# Spar7_rebuild.net
KiCad netlist of a schematic drawn in EAGLE
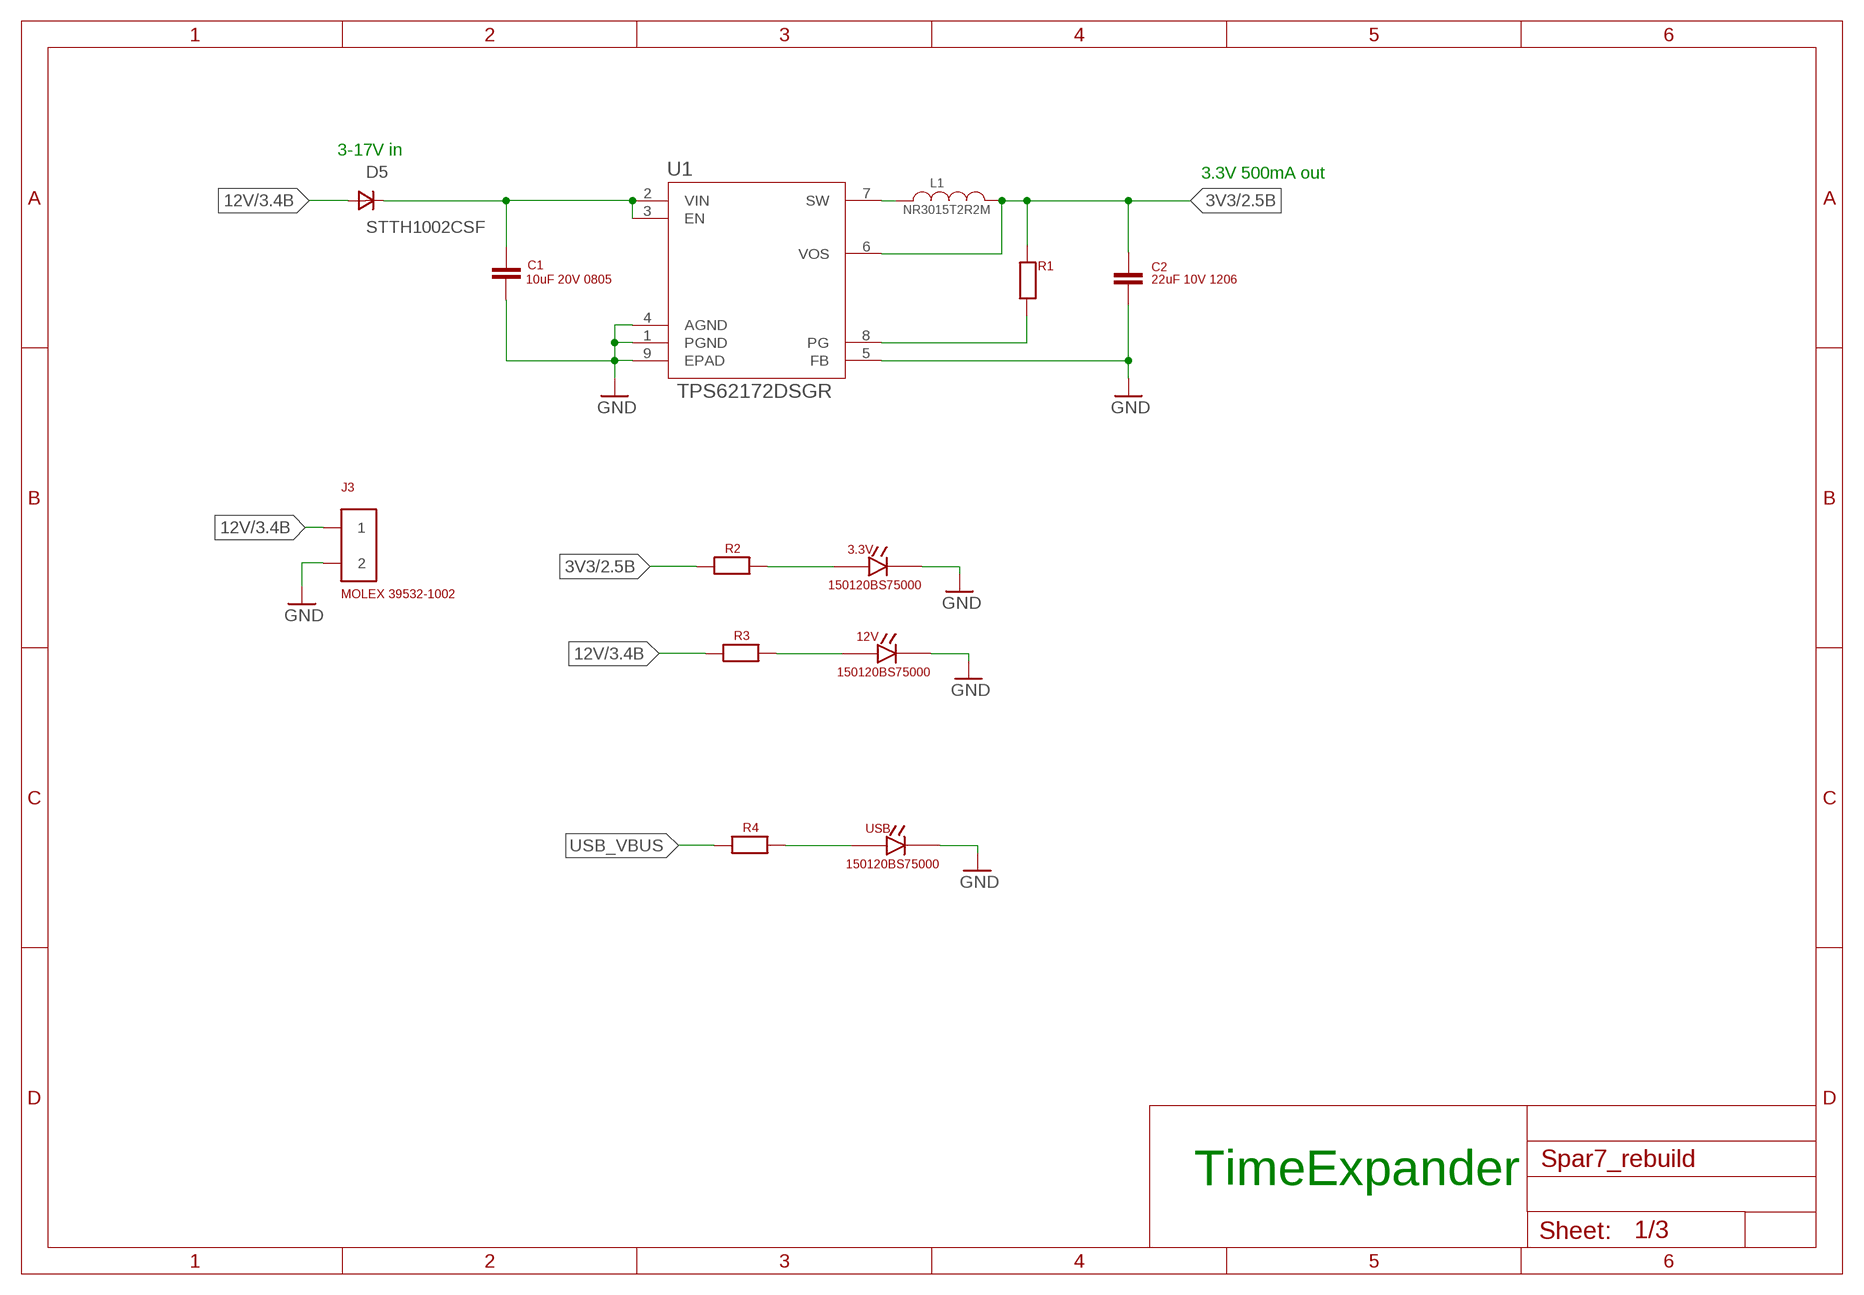
[diagram p0: schematic, sheet 1]
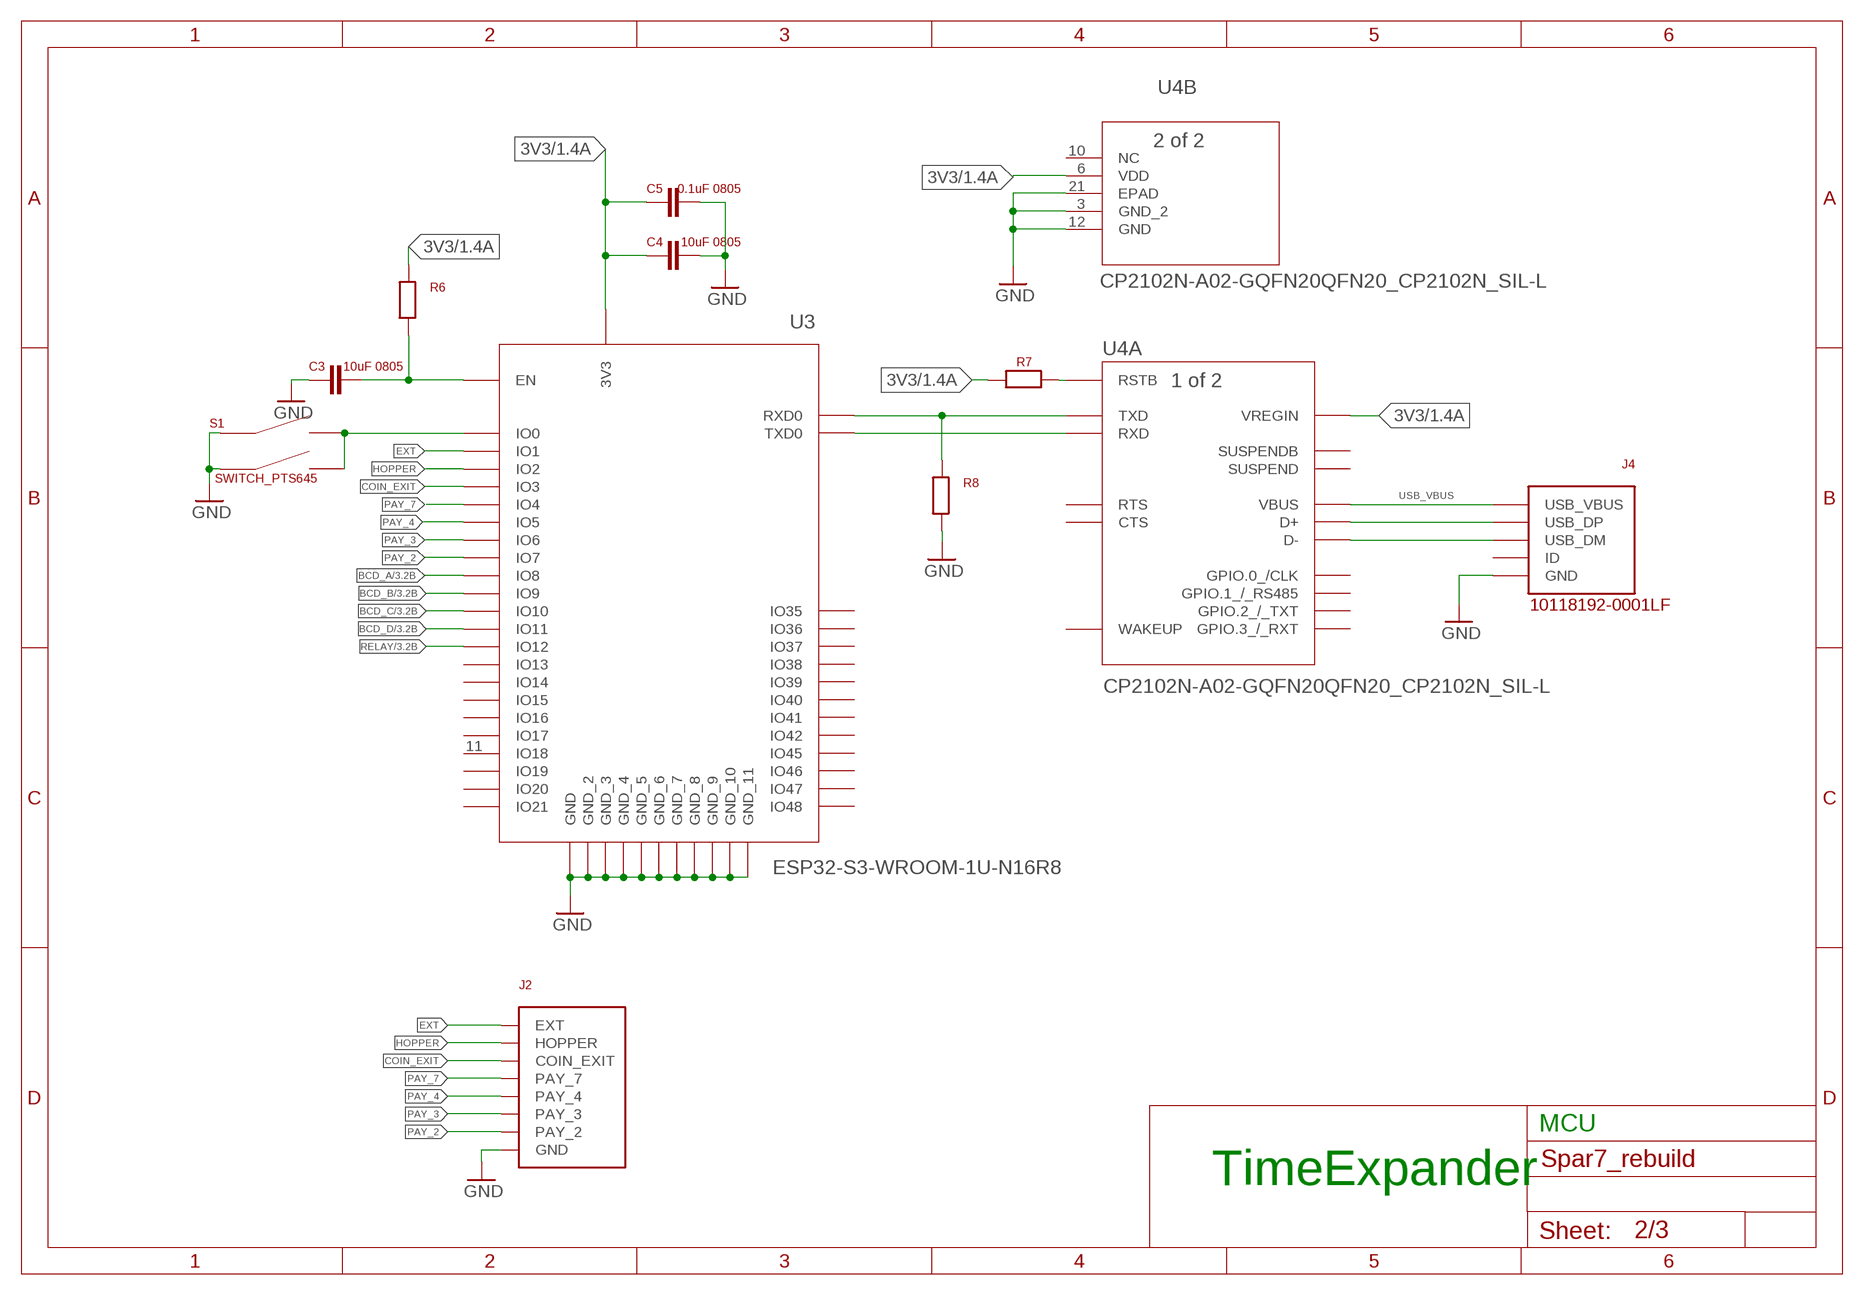
[diagram p1: schematic, sheet 2]
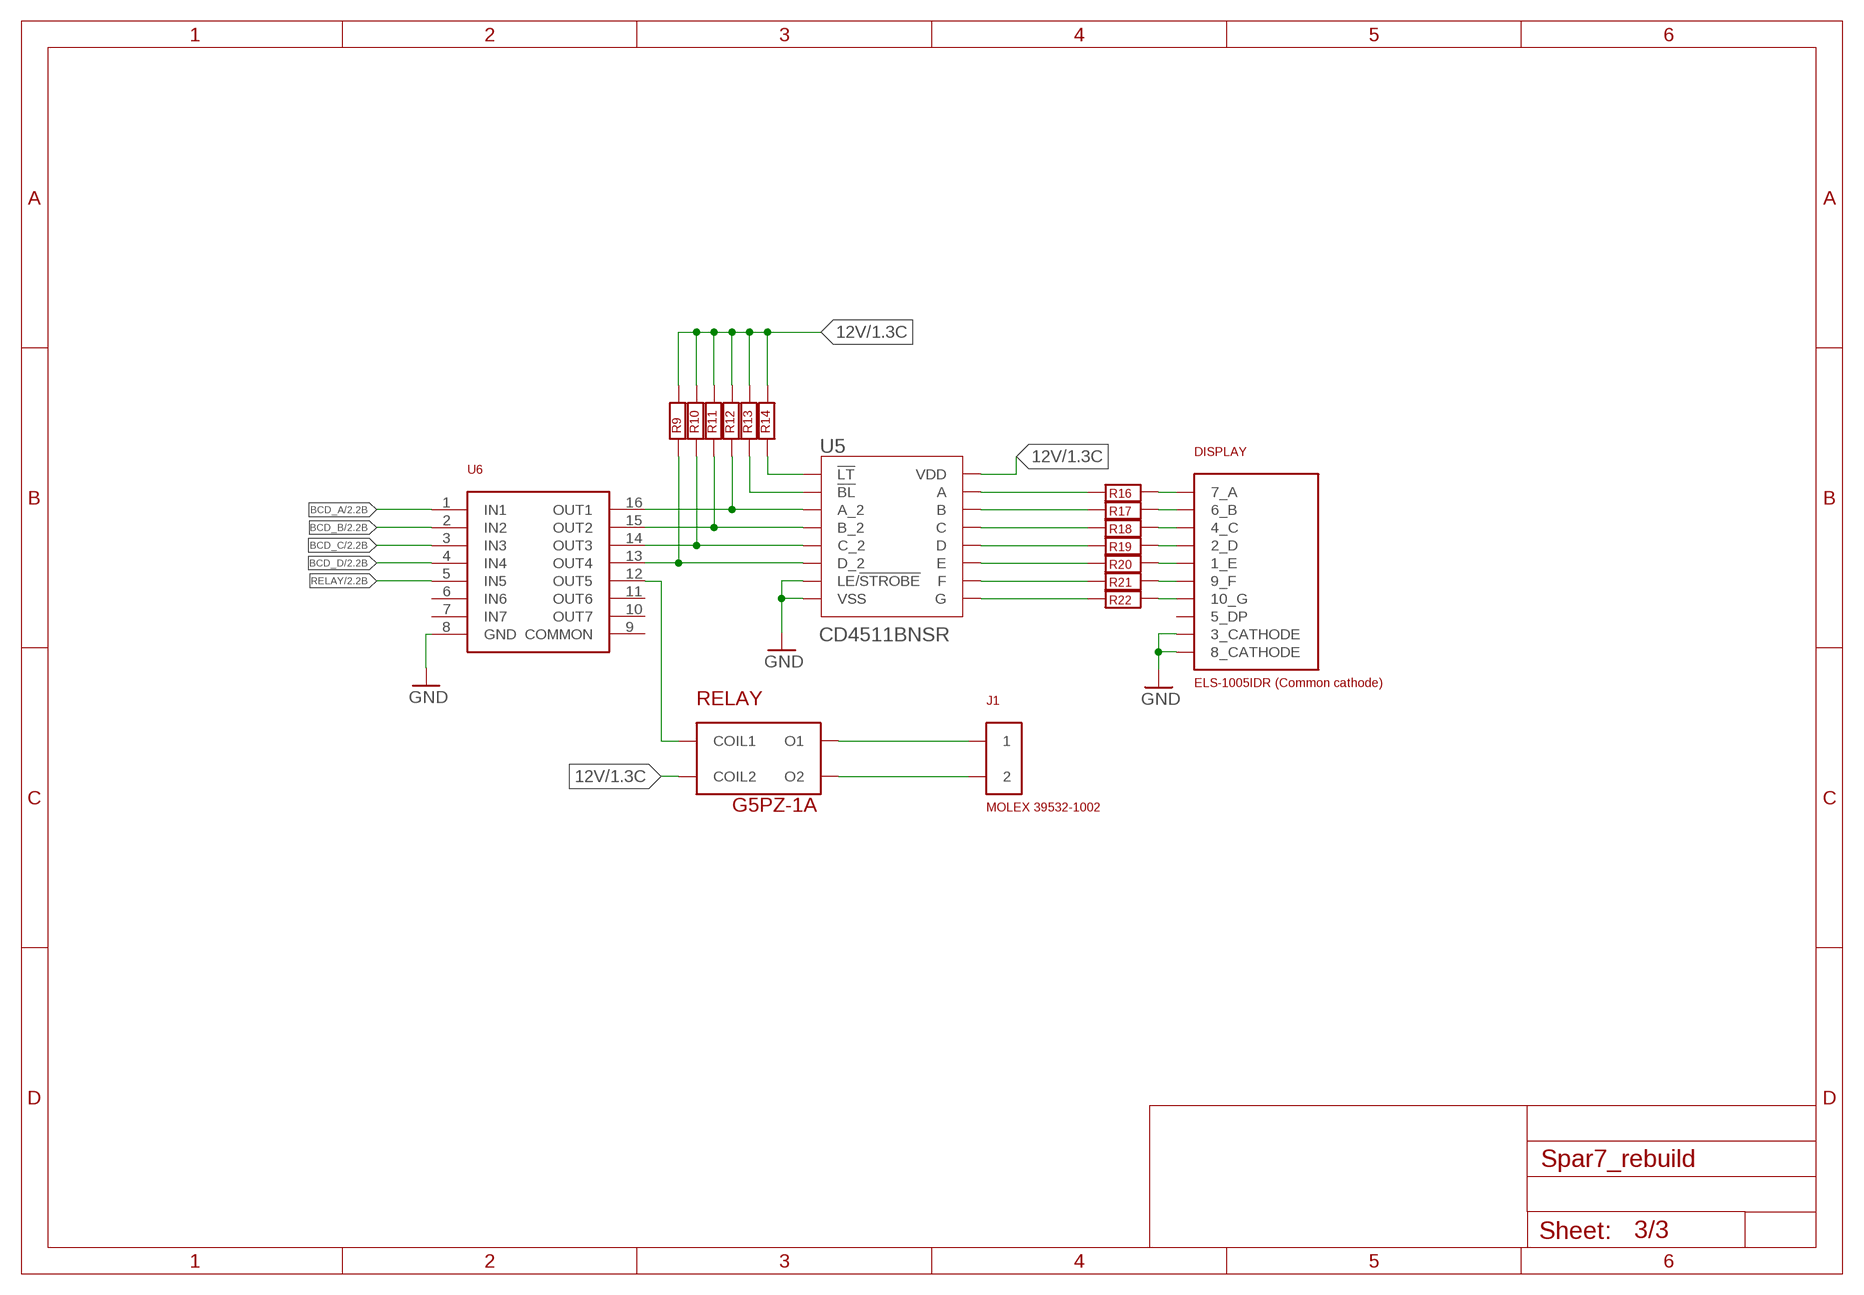
[diagram p2: schematic, sheet 3]

(export (version "E")
  (design (tool "Eeschema 10.0.6"))
  (components
    (comp (ref "C3")
      (value "10uF 0805")
      (footprint "eagle-import:CAP_0805")
      (libsource (lib "eagle-import") (part "CAPACITOR0805"))
    )
    (comp (ref "C4")
      (value "10uF 0805")
      (footprint "eagle-import:CAP_0805")
      (libsource (lib "eagle-import") (part "CAPACITOR0805"))
    )
    (comp (ref "C5")
      (value "0.1uF 0805")
      (footprint "eagle-import:CAP_0805")
      (libsource (lib "eagle-import") (part "CAPACITOR0805"))
    )
    (comp (ref "J2")
      (value "SPAR7_REWIRED_TERM_BLOCK")
      (footprint "eagle-import:SPAR7_REWIRED_TERM_BLOCK")
      (libsource (lib "eagle-import") (part "SPAR7_REWIRED_TERM_BLOCK"))
    )
    (comp (ref "J4")
      (value "10118192-0001LF")
      (footprint "eagle-import:USB_RCPT_10118192-0001LF")
      (libsource (lib "eagle-import") (part "USB_RCPT_10118192-0001LF"))
    )
    (comp (ref "R6")
      (value "RESISTOR0402")
      (footprint "eagle-import:RES_0402")
      (libsource (lib "eagle-import") (part "RESISTOR0402"))
    )
    (comp (ref "R7")
      (value "RESISTOR0402")
      (footprint "eagle-import:RES_0402")
      (libsource (lib "eagle-import") (part "RESISTOR0402"))
    )
    (comp (ref "R8")
      (value "RESISTOR0402")
      (footprint "eagle-import:RES_0402")
      (libsource (lib "eagle-import") (part "RESISTOR0402"))
    )
    (comp (ref "S1")
      (value "SWITCH_PTS645")
      (footprint "eagle-import:SWITCH_PTS645_EE_NBIOT_01")
      (libsource (lib "eagle-import") (part "SWITCH_PTS645"))
    )
    (comp (ref "U3")
      (value "ESP32-S3-WROOM-1U-N16R8")
      (footprint "eagle-import:ESP32­S3­WROOM­1U_EXP")
      (fields (field (name "COPYRIGHT") "Copyright (C) 2023 Ultra Librarian. All rights reserved."))
      (libsource (lib "eagle-import") (part "ESP32-S3-WROOM-1U-N16R8"))
    )
    (comp (ref "U4")
      (value "CP2102N-A02-GQFN20QFN20_CP2102N_SIL-L")
      (footprint "eagle-import:QFN20_CP2102N_SIL-L")
      (fields
        (field (name "MANUFACTURER_PART_NUMBER") "CP2102N-A02-GQFN20")
        (field (name "COPYRIGHT") "Copyright (C) 2023 Ultra Librarian. All rights reserved.")
      )
      (libsource (lib "eagle-import") (part "CP2102N-A02-GQFN20QFN20_CP2102N_SIL-L"))
    )
    (comp (ref "3.3V")
      (value "150120BS75000")
      (footprint "eagle-import:150120BS75000")
      (libsource (lib "eagle-import") (part "LED150120BS75000"))
    )
    (comp (ref "12V")
      (value "150120BS75000")
      (footprint "eagle-import:150120BS75000")
      (libsource (lib "eagle-import") (part "LED150120BS75000"))
    )
    (comp (ref "C1")
      (value "10uF 20V 0805")
      (footprint "eagle-import:CAP_0805")
      (libsource (lib "eagle-import") (part "CAPACITOR0805"))
    )
    (comp (ref "C2")
      (value "22uF 10V 1206")
      (footprint "eagle-import:CAP_1206")
      (libsource (lib "eagle-import") (part "CAPACITOR1206"))
    )
    (comp (ref "D5")
      (value "STTH1002CSF")
      (footprint "eagle-import:DIODE_STTH1002CSF")
      (libsource (lib "eagle-import") (part "DIODESTTH1002CSF"))
    )
    (comp (ref "J3")
      (value "MOLEX-39532-1002")
      (footprint "eagle-import:MOLEX-39532-1002")
      (libsource (lib "eagle-import") (part "MOLEX-39532-1002"))
    )
    (comp (ref "L1")
      (value "NR3015T2R2M")
      (footprint "eagle-import:IND_TAIYO_NR3015_TAY")
      (libsource (lib "eagle-import") (part "NR3015T2R2M"))
    )
    (comp (ref "R1")
      (value "RESISTOR0402")
      (footprint "eagle-import:RES_0402")
      (libsource (lib "eagle-import") (part "RESISTOR0402"))
    )
    (comp (ref "R2")
      (value "RESISTOR0402")
      (footprint "eagle-import:RES_0402")
      (libsource (lib "eagle-import") (part "RESISTOR0402"))
    )
    (comp (ref "R3")
      (value "RESISTOR0402")
      (footprint "eagle-import:RES_0402")
      (libsource (lib "eagle-import") (part "RESISTOR0402"))
    )
    (comp (ref "R4")
      (value "RESISTOR0402")
      (footprint "eagle-import:RES_0402")
      (libsource (lib "eagle-import") (part "RESISTOR0402"))
    )
    (comp (ref "U1")
      (value "TPS62172DSGR")
      (footprint "eagle-import:DSG8_1P6X0P9")
      (fields
        (field (name "GENERIC_PART_NUMBER") "TPS62173")
        (field (name "MANUFACTURER") "Texas Instruments")
        (field (name "MANUFACTURER_PART_NUMBER") "TPS62173DSGR")
      )
      (libsource (lib "eagle-import") (part "TPS62173DSGR"))
    )
    (comp (ref "USB")
      (value "150120BS75000")
      (footprint "eagle-import:150120BS75000")
      (libsource (lib "eagle-import") (part "LED150120BS75000"))
    )
    (comp (ref "DISPLAY")
      (value "ELS-1005IDR-SA10-21EWA")
      (footprint "eagle-import:ELS-1005IDR-SA10-21EWA")
      (libsource (lib "eagle-import") (part "ELS-1005IDR-SA10-21EWA"))
    )
    (comp (ref "J1")
      (value "MOLEX-39532-1002")
      (footprint "eagle-import:MOLEX-39532-1002")
      (libsource (lib "eagle-import") (part "MOLEX-39532-1002"))
    )
    (comp (ref "R9")
      (value "RESISTOR0402")
      (footprint "eagle-import:RES_0402")
      (libsource (lib "eagle-import") (part "RESISTOR0402"))
    )
    (comp (ref "R10")
      (value "RESISTOR0402")
      (footprint "eagle-import:RES_0402")
      (libsource (lib "eagle-import") (part "RESISTOR0402"))
    )
    (comp (ref "R11")
      (value "RESISTOR0402")
      (footprint "eagle-import:RES_0402")
      (libsource (lib "eagle-import") (part "RESISTOR0402"))
    )
    (comp (ref "R12")
      (value "RESISTOR0402")
      (footprint "eagle-import:RES_0402")
      (libsource (lib "eagle-import") (part "RESISTOR0402"))
    )
    (comp (ref "R13")
      (value "RESISTOR0402")
      (footprint "eagle-import:RES_0402")
      (libsource (lib "eagle-import") (part "RESISTOR0402"))
    )
    (comp (ref "R14")
      (value "RESISTOR0402")
      (footprint "eagle-import:RES_0402")
      (libsource (lib "eagle-import") (part "RESISTOR0402"))
    )
    (comp (ref "R16")
      (value "RESISTOR0402")
      (footprint "eagle-import:RES_0402")
      (libsource (lib "eagle-import") (part "RESISTOR0402"))
    )
    (comp (ref "R17")
      (value "RESISTOR0402")
      (footprint "eagle-import:RES_0402")
      (libsource (lib "eagle-import") (part "RESISTOR0402"))
    )
    (comp (ref "R18")
      (value "RESISTOR0402")
      (footprint "eagle-import:RES_0402")
      (libsource (lib "eagle-import") (part "RESISTOR0402"))
    )
    (comp (ref "R19")
      (value "RESISTOR0402")
      (footprint "eagle-import:RES_0402")
      (libsource (lib "eagle-import") (part "RESISTOR0402"))
    )
    (comp (ref "R20")
      (value "RESISTOR0402")
      (footprint "eagle-import:RES_0402")
      (libsource (lib "eagle-import") (part "RESISTOR0402"))
    )
    (comp (ref "R21")
      (value "RESISTOR0402")
      (footprint "eagle-import:RES_0402")
      (libsource (lib "eagle-import") (part "RESISTOR0402"))
    )
    (comp (ref "R22")
      (value "RESISTOR0402")
      (footprint "eagle-import:RES_0402")
      (libsource (lib "eagle-import") (part "RESISTOR0402"))
    )
    (comp (ref "RELAY")
      (value "G5PZ-1A_RELAY")
      (footprint "eagle-import:G5PZ-1A_RELAY")
      (libsource (lib "eagle-import") (part "G5PZ-1A_RELAY"))
    )
    (comp (ref "U5")
      (value "CD4511BNSR")
      (footprint "eagle-import:NS16")
      (fields (field (name "COPYRIGHT") "Copyright (C) 2023 Ultra Librarian. All rights reserved."))
      (libsource (lib "eagle-import") (part "CD4511BNSR"))
    )
    (comp (ref "U6")
      (value "ULN2003D1013TR")
      (footprint "eagle-import:SO16-NARROW")
      (libsource (lib "eagle-import") (part "ULN2003D1013TR"))
    )
  )
  (nets
    (net (code "1") (name "3V3") (class "Default")
      (node (ref "C2") (pin "P$1") (pinfunction "1_P$1") (pintype "passive"))
      (node (ref "C4") (pin "P$1") (pinfunction "1_P$1") (pintype "passive"))
      (node (ref "C5") (pin "P$1") (pinfunction "1_P$1") (pintype "passive"))
      (node (ref "L1") (pin "1") (pinfunction "1_1") (pintype "passive"))
      (node (ref "R1") (pin "P$1") (pinfunction "P$1_P$1") (pintype "bidirectional"))
      (node (ref "R2") (pin "P$1") (pinfunction "P$1_P$1") (pintype "bidirectional"))
      (node (ref "R6") (pin "P$2") (pinfunction "P$2_P$2") (pintype "bidirectional"))
      (node (ref "R7") (pin "P$1") (pinfunction "P$1_P$1") (pintype "bidirectional"))
      (node (ref "U1") (pin "6") (pinfunction "VOS_6") (pintype "input"))
      (node (ref "U3") (pin "2") (pinfunction "3V3_2") (pintype "power_in"))
      (node (ref "U4") (pin "6") (pinfunction "VDD_6") (pintype "power_in"))
      (node (ref "U4") (pin "7") (pinfunction "VREGIN_7") (pintype "passive"))
    )
    (net (code "2") (name "12V") (class "Default")
      (node (ref "D5") (pin "A1") (pinfunction "A_A1") (pintype "passive"))
      (node (ref "D5") (pin "A2") (pinfunction "A_A2") (pintype "passive"))
      (node (ref "J3") (pin "1") (pinfunction "1_1") (pintype "power_in"))
      (node (ref "R10") (pin "P$2") (pinfunction "P$2_P$2") (pintype "bidirectional"))
      (node (ref "R11") (pin "P$2") (pinfunction "P$2_P$2") (pintype "bidirectional"))
      (node (ref "R12") (pin "P$2") (pinfunction "P$2_P$2") (pintype "bidirectional"))
      (node (ref "R13") (pin "P$2") (pinfunction "P$2_P$2") (pintype "bidirectional"))
      (node (ref "R14") (pin "P$2") (pinfunction "P$2_P$2") (pintype "bidirectional"))
      (node (ref "R3") (pin "P$1") (pinfunction "P$1_P$1") (pintype "bidirectional"))
      (node (ref "R9") (pin "P$2") (pinfunction "P$2_P$2") (pintype "bidirectional"))
      (node (ref "RELAY") (pin "COIL2") (pinfunction "COIL2_COIL2") (pintype "power_in"))
      (node (ref "U5") (pin "16") (pinfunction "VDD_16") (pintype "power_in"))
    )
    (net (code "3") (name "BCD_A") (class "Default")
      (node (ref "U3") (pin "12") (pinfunction "IO8_12") (pintype "bidirectional"))
      (node (ref "U6") (pin "1") (pinfunction "IN1_1") (pintype "bidirectional"))
    )
    (net (code "4") (name "BCD_B") (class "Default")
      (node (ref "U3") (pin "17") (pinfunction "IO9_17") (pintype "bidirectional"))
      (node (ref "U6") (pin "2") (pinfunction "IN2_2") (pintype "bidirectional"))
    )
    (net (code "5") (name "BCD_C") (class "Default")
      (node (ref "U3") (pin "18") (pinfunction "IO10_18") (pintype "bidirectional"))
      (node (ref "U6") (pin "3") (pinfunction "IN3_3") (pintype "bidirectional"))
    )
    (net (code "6") (name "BCD_D") (class "Default")
      (node (ref "U3") (pin "19") (pinfunction "IO11_19") (pintype "bidirectional"))
      (node (ref "U6") (pin "4") (pinfunction "IN4_4") (pintype "bidirectional"))
    )
    (net (code "7") (name "COIN_EXIT") (class "Default")
      (node (ref "J2") (pin "COIN_EXIT") (pinfunction "COIN_EXIT_COIN_EXIT") (pintype "power_in"))
      (node (ref "U3") (pin "15") (pinfunction "IO3_15") (pintype "bidirectional"))
    )
    (net (code "8") (name "EXT") (class "Default")
      (node (ref "J2") (pin "EXT") (pinfunction "EXT_EXT") (pintype "power_in"))
      (node (ref "U3") (pin "39") (pinfunction "IO1_39") (pintype "bidirectional"))
    )
    (net (code "9") (name "GND") (class "Default")
      (node (ref "12V") (pin "C") (pinfunction "C_C") (pintype "passive"))
      (node (ref "3.3V") (pin "C") (pinfunction "C_C") (pintype "passive"))
      (node (ref "C1") (pin "P$2") (pinfunction "2_P$2") (pintype "passive"))
      (node (ref "C2") (pin "P$2") (pinfunction "2_P$2") (pintype "passive"))
      (node (ref "C3") (pin "P$1") (pinfunction "1_P$1") (pintype "passive"))
      (node (ref "C4") (pin "P$2") (pinfunction "2_P$2") (pintype "passive"))
      (node (ref "C5") (pin "P$2") (pinfunction "2_P$2") (pintype "passive"))
      (node (ref "DISPLAY") (pin "3_CATHODE") (pinfunction "3_CATHODE_3_CATHODE") (pintype "bidirectional"))
      (node (ref "DISPLAY") (pin "8_CATHODE") (pinfunction "8_CATHODE_8_CATHODE") (pintype "bidirectional"))
      (node (ref "J2") (pin "GND") (pinfunction "GND_GND") (pintype "power_in"))
      (node (ref "J3") (pin "2") (pinfunction "2_2") (pintype "power_in"))
      (node (ref "J4") (pin "GND") (pinfunction "GND_GND") (pintype "passive"))
      (node (ref "R8") (pin "P$1") (pinfunction "P$1_P$1") (pintype "bidirectional"))
      (node (ref "S1") (pin "A1") (pinfunction "A1_A1") (pintype "bidirectional"))
      (node (ref "S1") (pin "A2") (pinfunction "A2_A2") (pintype "bidirectional"))
      (node (ref "U1") (pin "1") (pinfunction "PGND_1") (pintype "power_in"))
      (node (ref "U1") (pin "4") (pinfunction "AGND_4") (pintype "power_in"))
      (node (ref "U1") (pin "5") (pinfunction "FB_5") (pintype "input"))
      (node (ref "U1") (pin "9") (pinfunction "EPAD_9") (pintype "input"))
      (node (ref "U3") (pin "1") (pinfunction "GND_2_1") (pintype "passive"))
      (node (ref "U3") (pin "40") (pinfunction "GND_3_40") (pintype "passive"))
      (node (ref "U3") (pin "41") (pinfunction "GND_4_41") (pintype "passive"))
      (node (ref "U3") (pin "42") (pinfunction "GND_5_42") (pintype "passive"))
      (node (ref "U3") (pin "43") (pinfunction "GND_6_43") (pintype "passive"))
      (node (ref "U3") (pin "44") (pinfunction "GND_7_44") (pintype "passive"))
      (node (ref "U3") (pin "45") (pinfunction "GND_8_45") (pintype "passive"))
      (node (ref "U3") (pin "46") (pinfunction "GND_9_46") (pintype "passive"))
      (node (ref "U3") (pin "47") (pinfunction "GND_10_47") (pintype "passive"))
      (node (ref "U3") (pin "48") (pinfunction "GND_11_48") (pintype "passive"))
      (node (ref "U3") (pin "49") (pinfunction "GND_49") (pintype "passive"))
      (node (ref "U4") (pin "12") (pinfunction "GND_12") (pintype "passive"))
      (node (ref "U4") (pin "21") (pinfunction "EPAD_21") (pintype "passive"))
      (node (ref "U4") (pin "3") (pinfunction "GND_2_3") (pintype "passive"))
      (node (ref "U5") (pin "5") (pinfunction "LE/~{STROBE}_5") (pintype "passive"))
      (node (ref "U5") (pin "8") (pinfunction "VSS_8") (pintype "power_in"))
      (node (ref "U6") (pin "8") (pinfunction "GND_8") (pintype "bidirectional"))
      (node (ref "USB") (pin "C") (pinfunction "C_C") (pintype "passive"))
    )
    (net (code "10") (name "HOPPER") (class "Default")
      (node (ref "J2") (pin "HOPPER") (pinfunction "HOPPER_HOPPER") (pintype "power_in"))
      (node (ref "U3") (pin "38") (pinfunction "IO2_38") (pintype "bidirectional"))
    )
    (net (code "11") (name "Net-(3.3V-PadA)") (class "Default")
      (node (ref "3.3V") (pin "A") (pinfunction "A_A") (pintype "passive"))
      (node (ref "R2") (pin "P$2") (pinfunction "P$2_P$2") (pintype "bidirectional"))
    )
    (net (code "12") (name "Net-(12V-PadA)") (class "Default")
      (node (ref "12V") (pin "A") (pinfunction "A_A") (pintype "passive"))
      (node (ref "R3") (pin "P$2") (pinfunction "P$2_P$2") (pintype "bidirectional"))
    )
    (net (code "13") (name "Net-(C1-1)") (class "Default")
      (node (ref "C1") (pin "P$1") (pinfunction "1_P$1") (pintype "passive"))
      (node (ref "D5") (pin "C") (pinfunction "C_C") (pintype "passive"))
      (node (ref "U1") (pin "2") (pinfunction "VIN_2") (pintype "input"))
      (node (ref "U1") (pin "3") (pinfunction "EN_3") (pintype "input"))
    )
    (net (code "14") (name "Net-(C3-2)") (class "Default")
      (node (ref "C3") (pin "P$2") (pinfunction "2_P$2") (pintype "passive"))
      (node (ref "R6") (pin "P$1") (pinfunction "P$1_P$1") (pintype "bidirectional"))
      (node (ref "U3") (pin "3") (pinfunction "EN_3") (pintype "input"))
    )
    (net (code "15") (name "Net-(DISPLAY-Pad1_E)") (class "Default")
      (node (ref "DISPLAY") (pin "1_E") (pinfunction "1_E_1_E") (pintype "bidirectional"))
      (node (ref "R20") (pin "P$1") (pinfunction "P$1_P$1") (pintype "bidirectional"))
    )
    (net (code "16") (name "Net-(DISPLAY-Pad2_D)") (class "Default")
      (node (ref "DISPLAY") (pin "2_D") (pinfunction "2_D_2_D") (pintype "bidirectional"))
      (node (ref "R19") (pin "P$1") (pinfunction "P$1_P$1") (pintype "bidirectional"))
    )
    (net (code "17") (name "Net-(DISPLAY-Pad4_C)") (class "Default")
      (node (ref "DISPLAY") (pin "4_C") (pinfunction "4_C_4_C") (pintype "bidirectional"))
      (node (ref "R18") (pin "P$1") (pinfunction "P$1_P$1") (pintype "bidirectional"))
    )
    (net (code "18") (name "Net-(DISPLAY-Pad6_B)") (class "Default")
      (node (ref "DISPLAY") (pin "6_B") (pinfunction "6_B_6_B") (pintype "bidirectional"))
      (node (ref "R17") (pin "P$1") (pinfunction "P$1_P$1") (pintype "bidirectional"))
    )
    (net (code "19") (name "Net-(DISPLAY-Pad7_A)") (class "Default")
      (node (ref "DISPLAY") (pin "7_A") (pinfunction "7_A_7_A") (pintype "bidirectional"))
      (node (ref "R16") (pin "P$1") (pinfunction "P$1_P$1") (pintype "bidirectional"))
    )
    (net (code "20") (name "Net-(DISPLAY-Pad9_F)") (class "Default")
      (node (ref "DISPLAY") (pin "9_F") (pinfunction "9_F_9_F") (pintype "bidirectional"))
      (node (ref "R21") (pin "P$1") (pinfunction "P$1_P$1") (pintype "bidirectional"))
    )
    (net (code "21") (name "Net-(DISPLAY-Pad10_G)") (class "Default")
      (node (ref "DISPLAY") (pin "10_G") (pinfunction "10_G_10_G") (pintype "bidirectional"))
      (node (ref "R22") (pin "P$1") (pinfunction "P$1_P$1") (pintype "bidirectional"))
    )
    (net (code "22") (name "Net-(J1-Pad1)") (class "Default")
      (node (ref "J1") (pin "1") (pinfunction "1_1") (pintype "power_in"))
      (node (ref "RELAY") (pin "O1") (pinfunction "O1_O1") (pintype "power_in"))
    )
    (net (code "23") (name "Net-(J1-Pad2)") (class "Default")
      (node (ref "J1") (pin "2") (pinfunction "2_2") (pintype "power_in"))
      (node (ref "RELAY") (pin "O2") (pinfunction "O2_O2") (pintype "power_in"))
    )
    (net (code "24") (name "Net-(J4-USB_DM)") (class "Default")
      (node (ref "J4") (pin "D-") (pinfunction "USB_DM_D-") (pintype "passive"))
      (node (ref "U4") (pin "5") (pinfunction "D-_5") (pintype "passive"))
    )
    (net (code "25") (name "Net-(J4-USB_DP)") (class "Default")
      (node (ref "J4") (pin "D+") (pinfunction "USB_DP_D+") (pintype "passive"))
      (node (ref "U4") (pin "4") (pinfunction "D+_4") (pintype "passive"))
    )
    (net (code "26") (name "Net-(R4-PadP$2)") (class "Default")
      (node (ref "R4") (pin "P$2") (pinfunction "P$2_P$2") (pintype "bidirectional"))
      (node (ref "USB") (pin "A") (pinfunction "A_A") (pintype "passive"))
    )
    (net (code "27") (name "Net-(U1-PG)") (class "Default")
      (node (ref "R1") (pin "P$2") (pinfunction "P$2_P$2") (pintype "bidirectional"))
      (node (ref "U1") (pin "8") (pinfunction "PG_8") (pintype "input"))
    )
    (net (code "28") (name "Net-(U1-SW)") (class "Default")
      (node (ref "L1") (pin "2") (pinfunction "2_2") (pintype "passive"))
      (node (ref "U1") (pin "7") (pinfunction "SW_7") (pintype "output"))
    )
    (net (code "29") (name "Net-(U3-IO0)") (class "Default")
      (node (ref "S1") (pin "B1") (pinfunction "B1_B1") (pintype "bidirectional"))
      (node (ref "S1") (pin "B2") (pinfunction "B2_B2") (pintype "bidirectional"))
      (node (ref "U3") (pin "27") (pinfunction "IO0_27") (pintype "bidirectional"))
    )
    (net (code "30") (name "Net-(U3-RXD0)") (class "Default")
      (node (ref "R8") (pin "P$2") (pinfunction "P$2_P$2") (pintype "bidirectional"))
      (node (ref "U3") (pin "36") (pinfunction "RXD0_36") (pintype "bidirectional"))
      (node (ref "U4") (pin "18") (pinfunction "TXD_18") (pintype "passive"))
    )
    (net (code "31") (name "Net-(U3-TXD0)") (class "Default")
      (node (ref "U3") (pin "37") (pinfunction "TXD0_37") (pintype "bidirectional"))
      (node (ref "U4") (pin "17") (pinfunction "RXD_17") (pintype "passive"))
    )
    (net (code "32") (name "Net-(U4A-RSTB)") (class "Default")
      (node (ref "R7") (pin "P$2") (pinfunction "P$2_P$2") (pintype "bidirectional"))
      (node (ref "U4") (pin "9") (pinfunction "RSTB_9") (pintype "passive"))
    )
    (net (code "33") (name "Net-(U5-A)") (class "Default")
      (node (ref "R16") (pin "P$2") (pinfunction "P$2_P$2") (pintype "bidirectional"))
      (node (ref "U5") (pin "13") (pinfunction "A_13") (pintype "passive"))
    )
    (net (code "34") (name "Net-(U5-A_2)") (class "Default")
      (node (ref "R12") (pin "P$1") (pinfunction "P$1_P$1") (pintype "bidirectional"))
      (node (ref "U5") (pin "7") (pinfunction "A_2_7") (pintype "passive"))
      (node (ref "U6") (pin "16") (pinfunction "OUT1_16") (pintype "bidirectional"))
    )
    (net (code "35") (name "Net-(U5-B)") (class "Default")
      (node (ref "R17") (pin "P$2") (pinfunction "P$2_P$2") (pintype "bidirectional"))
      (node (ref "U5") (pin "12") (pinfunction "B_12") (pintype "passive"))
    )
    (net (code "36") (name "Net-(U5-B_2)") (class "Default")
      (node (ref "R11") (pin "P$1") (pinfunction "P$1_P$1") (pintype "bidirectional"))
      (node (ref "U5") (pin "1") (pinfunction "B_2_1") (pintype "passive"))
      (node (ref "U6") (pin "15") (pinfunction "OUT2_15") (pintype "bidirectional"))
    )
    (net (code "37") (name "Net-(U5-C)") (class "Default")
      (node (ref "R18") (pin "P$2") (pinfunction "P$2_P$2") (pintype "bidirectional"))
      (node (ref "U5") (pin "11") (pinfunction "C_11") (pintype "passive"))
    )
    (net (code "38") (name "Net-(U5-C_2)") (class "Default")
      (node (ref "R10") (pin "P$1") (pinfunction "P$1_P$1") (pintype "bidirectional"))
      (node (ref "U5") (pin "2") (pinfunction "C_2_2") (pintype "passive"))
      (node (ref "U6") (pin "14") (pinfunction "OUT3_14") (pintype "bidirectional"))
    )
    (net (code "39") (name "Net-(U5-D)") (class "Default")
      (node (ref "R19") (pin "P$2") (pinfunction "P$2_P$2") (pintype "bidirectional"))
      (node (ref "U5") (pin "10") (pinfunction "D_10") (pintype "passive"))
    )
    (net (code "40") (name "Net-(U5-D_2)") (class "Default")
      (node (ref "R9") (pin "P$1") (pinfunction "P$1_P$1") (pintype "bidirectional"))
      (node (ref "U5") (pin "6") (pinfunction "D_2_6") (pintype "passive"))
      (node (ref "U6") (pin "13") (pinfunction "OUT4_13") (pintype "bidirectional"))
    )
    (net (code "41") (name "Net-(U5-E)") (class "Default")
      (node (ref "R20") (pin "P$2") (pinfunction "P$2_P$2") (pintype "bidirectional"))
      (node (ref "U5") (pin "9") (pinfunction "E_9") (pintype "passive"))
    )
    (net (code "42") (name "Net-(U5-F)") (class "Default")
      (node (ref "R21") (pin "P$2") (pinfunction "P$2_P$2") (pintype "bidirectional"))
      (node (ref "U5") (pin "15") (pinfunction "F_15") (pintype "passive"))
    )
    (net (code "43") (name "Net-(U5-G)") (class "Default")
      (node (ref "R22") (pin "P$2") (pinfunction "P$2_P$2") (pintype "bidirectional"))
      (node (ref "U5") (pin "14") (pinfunction "G_14") (pintype "passive"))
    )
    (net (code "44") (name "Net-(U5-~{BL})") (class "Default")
      (node (ref "R13") (pin "P$1") (pinfunction "P$1_P$1") (pintype "bidirectional"))
      (node (ref "U5") (pin "4") (pinfunction "~{BL}_4") (pintype "passive"))
    )
    (net (code "45") (name "Net-(U5-~{LT})") (class "Default")
      (node (ref "R14") (pin "P$1") (pinfunction "P$1_P$1") (pintype "bidirectional"))
      (node (ref "U5") (pin "3") (pinfunction "~{LT}_3") (pintype "passive"))
    )
    (net (code "46") (name "Net-(U6-OUT5)") (class "Default")
      (node (ref "RELAY") (pin "COIL1") (pinfunction "COIL1_COIL1") (pintype "power_in"))
      (node (ref "U6") (pin "12") (pinfunction "OUT5_12") (pintype "bidirectional"))
    )
    (net (code "47") (name "PAY_2") (class "Default")
      (node (ref "J2") (pin "PAY_2") (pinfunction "PAY_2_PAY_2") (pintype "power_in"))
      (node (ref "U3") (pin "7") (pinfunction "IO7_7") (pintype "bidirectional"))
    )
    (net (code "48") (name "PAY_3") (class "Default")
      (node (ref "J2") (pin "PAY_3") (pinfunction "PAY_3_PAY_3") (pintype "power_in"))
      (node (ref "U3") (pin "6") (pinfunction "IO6_6") (pintype "bidirectional"))
    )
    (net (code "49") (name "PAY_4") (class "Default")
      (node (ref "J2") (pin "PAY_4") (pinfunction "PAY_4_PAY_4") (pintype "power_in"))
      (node (ref "U3") (pin "5") (pinfunction "IO5_5") (pintype "bidirectional"))
    )
    (net (code "50") (name "PAY_7") (class "Default")
      (node (ref "J2") (pin "PAY_7") (pinfunction "PAY_7_PAY_7") (pintype "power_in"))
      (node (ref "U3") (pin "4") (pinfunction "IO4_4") (pintype "bidirectional"))
    )
    (net (code "51") (name "RELAY") (class "Default")
      (node (ref "U3") (pin "20") (pinfunction "IO12_20") (pintype "bidirectional"))
      (node (ref "U6") (pin "5") (pinfunction "IN5_5") (pintype "bidirectional"))
    )
    (net (code "52") (name "USB_VBUS") (class "Default")
      (node (ref "J4") (pin "VCC") (pinfunction "USB_VBUS_VCC") (pintype "passive"))
      (node (ref "R4") (pin "P$1") (pinfunction "P$1_P$1") (pintype "bidirectional"))
      (node (ref "U4") (pin "8") (pinfunction "VBUS_8") (pintype "passive"))
    )
    (net (code "53") (name "unconnected-(DISPLAY-Pad5_DP)") (class "Default")
      (node (ref "DISPLAY") (pin "5_DP") (pinfunction "5_DP_5_DP") (pintype "bidirectional"))
    )
    (net (code "54") (name "unconnected-(J4-PadID)") (class "Default")
      (node (ref "J4") (pin "ID") (pinfunction "ID_ID") (pintype "passive"))
    )
    (net (code "55") (name "unconnected-(U3-IO13-Pad21)") (class "Default")
      (node (ref "U3") (pin "21") (pinfunction "IO13_21") (pintype "bidirectional"))
    )
    (net (code "56") (name "unconnected-(U3-IO14-Pad22)") (class "Default")
      (node (ref "U3") (pin "22") (pinfunction "IO14_22") (pintype "bidirectional"))
    )
    (net (code "57") (name "unconnected-(U3-IO15-Pad8)") (class "Default")
      (node (ref "U3") (pin "8") (pinfunction "IO15_8") (pintype "bidirectional"))
    )
    (net (code "58") (name "unconnected-(U3-IO16-Pad9)") (class "Default")
      (node (ref "U3") (pin "9") (pinfunction "IO16_9") (pintype "bidirectional"))
    )
    (net (code "59") (name "unconnected-(U3-IO17-Pad10)") (class "Default")
      (node (ref "U3") (pin "10") (pinfunction "IO17_10") (pintype "bidirectional"))
    )
    (net (code "60") (name "unconnected-(U3-IO18-Pad11)") (class "Default")
      (node (ref "U3") (pin "11") (pinfunction "IO18_11") (pintype "bidirectional"))
    )
    (net (code "61") (name "unconnected-(U3-IO19-Pad13)") (class "Default")
      (node (ref "U3") (pin "13") (pinfunction "IO19_13") (pintype "bidirectional"))
    )
    (net (code "62") (name "unconnected-(U3-IO20-Pad14)") (class "Default")
      (node (ref "U3") (pin "14") (pinfunction "IO20_14") (pintype "bidirectional"))
    )
    (net (code "63") (name "unconnected-(U3-IO21-Pad23)") (class "Default")
      (node (ref "U3") (pin "23") (pinfunction "IO21_23") (pintype "bidirectional"))
    )
    (net (code "64") (name "unconnected-(U3-IO35-Pad28)") (class "Default")
      (node (ref "U3") (pin "28") (pinfunction "IO35_28") (pintype "bidirectional"))
    )
    (net (code "65") (name "unconnected-(U3-IO36-Pad29)") (class "Default")
      (node (ref "U3") (pin "29") (pinfunction "IO36_29") (pintype "bidirectional"))
    )
    (net (code "66") (name "unconnected-(U3-IO37-Pad30)") (class "Default")
      (node (ref "U3") (pin "30") (pinfunction "IO37_30") (pintype "bidirectional"))
    )
    (net (code "67") (name "unconnected-(U3-IO38-Pad31)") (class "Default")
      (node (ref "U3") (pin "31") (pinfunction "IO38_31") (pintype "bidirectional"))
    )
    (net (code "68") (name "unconnected-(U3-IO39-Pad32)") (class "Default")
      (node (ref "U3") (pin "32") (pinfunction "IO39_32") (pintype "bidirectional"))
    )
    (net (code "69") (name "unconnected-(U3-IO40-Pad33)") (class "Default")
      (node (ref "U3") (pin "33") (pinfunction "IO40_33") (pintype "bidirectional"))
    )
    (net (code "70") (name "unconnected-(U3-IO41-Pad34)") (class "Default")
      (node (ref "U3") (pin "34") (pinfunction "IO41_34") (pintype "bidirectional"))
    )
    (net (code "71") (name "unconnected-(U3-IO42-Pad35)") (class "Default")
      (node (ref "U3") (pin "35") (pinfunction "IO42_35") (pintype "bidirectional"))
    )
    (net (code "72") (name "unconnected-(U3-IO45-Pad26)") (class "Default")
      (node (ref "U3") (pin "26") (pinfunction "IO45_26") (pintype "bidirectional"))
    )
    (net (code "73") (name "unconnected-(U3-IO46-Pad16)") (class "Default")
      (node (ref "U3") (pin "16") (pinfunction "IO46_16") (pintype "bidirectional"))
    )
    (net (code "74") (name "unconnected-(U3-IO47-Pad24)") (class "Default")
      (node (ref "U3") (pin "24") (pinfunction "IO47_24") (pintype "bidirectional"))
    )
    (net (code "75") (name "unconnected-(U3-IO48-Pad25)") (class "Default")
      (node (ref "U3") (pin "25") (pinfunction "IO48_25") (pintype "bidirectional"))
    )
    (net (code "76") (name "unconnected-(U4A-CTS-Pad15)") (class "Default")
      (node (ref "U4") (pin "15") (pinfunction "CTS_15") (pintype "passive"))
    )
    (net (code "77") (name "unconnected-(U4A-GPIO.0_{slash}CLK-Pad2)") (class "Default")
      (node (ref "U4") (pin "2") (pinfunction "GPIO.0_/CLK_2") (pintype "bidirectional"))
    )
    (net (code "78") (name "unconnected-(U4A-GPIO.1_{slash}_RS485-Pad1)") (class "Default")
      (node (ref "U4") (pin "1") (pinfunction "GPIO.1_/_RS485_1") (pintype "bidirectional"))
    )
    (net (code "79") (name "unconnected-(U4A-GPIO.2_{slash}_TXT-Pad20)") (class "Default")
      (node (ref "U4") (pin "20") (pinfunction "GPIO.2_/_TXT_20") (pintype "bidirectional"))
    )
    (net (code "80") (name "unconnected-(U4A-GPIO.3_{slash}_RXT-Pad19)") (class "Default")
      (node (ref "U4") (pin "19") (pinfunction "GPIO.3_/_RXT_19") (pintype "bidirectional"))
    )
    (net (code "81") (name "unconnected-(U4A-RTS-Pad16)") (class "Default")
      (node (ref "U4") (pin "16") (pinfunction "RTS_16") (pintype "passive"))
    )
    (net (code "82") (name "unconnected-(U4A-SUSPEND-Pad14)") (class "Default")
      (node (ref "U4") (pin "14") (pinfunction "SUSPEND_14") (pintype "passive"))
    )
    (net (code "83") (name "unconnected-(U4A-SUSPENDB-Pad11)") (class "Default")
      (node (ref "U4") (pin "11") (pinfunction "SUSPENDB_11") (pintype "passive"))
    )
    (net (code "84") (name "unconnected-(U4A-WAKEUP-Pad13)") (class "Default")
      (node (ref "U4") (pin "13") (pinfunction "WAKEUP_13") (pintype "passive"))
    )
    (net (code "85") (name "unconnected-(U4B-NC-Pad10)") (class "Default")
      (node (ref "U4") (pin "10") (pinfunction "NC_10") (pintype "no_connect"))
    )
    (net (code "86") (name "unconnected-(U6-COMMON-Pad9)") (class "Default")
      (node (ref "U6") (pin "9") (pinfunction "COMMON_9") (pintype "bidirectional"))
    )
    (net (code "87") (name "unconnected-(U6-IN6-Pad6)") (class "Default")
      (node (ref "U6") (pin "6") (pinfunction "IN6_6") (pintype "bidirectional"))
    )
    (net (code "88") (name "unconnected-(U6-IN7-Pad7)") (class "Default")
      (node (ref "U6") (pin "7") (pinfunction "IN7_7") (pintype "bidirectional"))
    )
    (net (code "89") (name "unconnected-(U6-OUT6-Pad11)") (class "Default")
      (node (ref "U6") (pin "11") (pinfunction "OUT6_11") (pintype "bidirectional"))
    )
    (net (code "90") (name "unconnected-(U6-OUT7-Pad10)") (class "Default")
      (node (ref "U6") (pin "10") (pinfunction "OUT7_10") (pintype "bidirectional"))
    )
  )
)
